# receivera.net
KiCad netlist of a schematic drawn in EAGLE
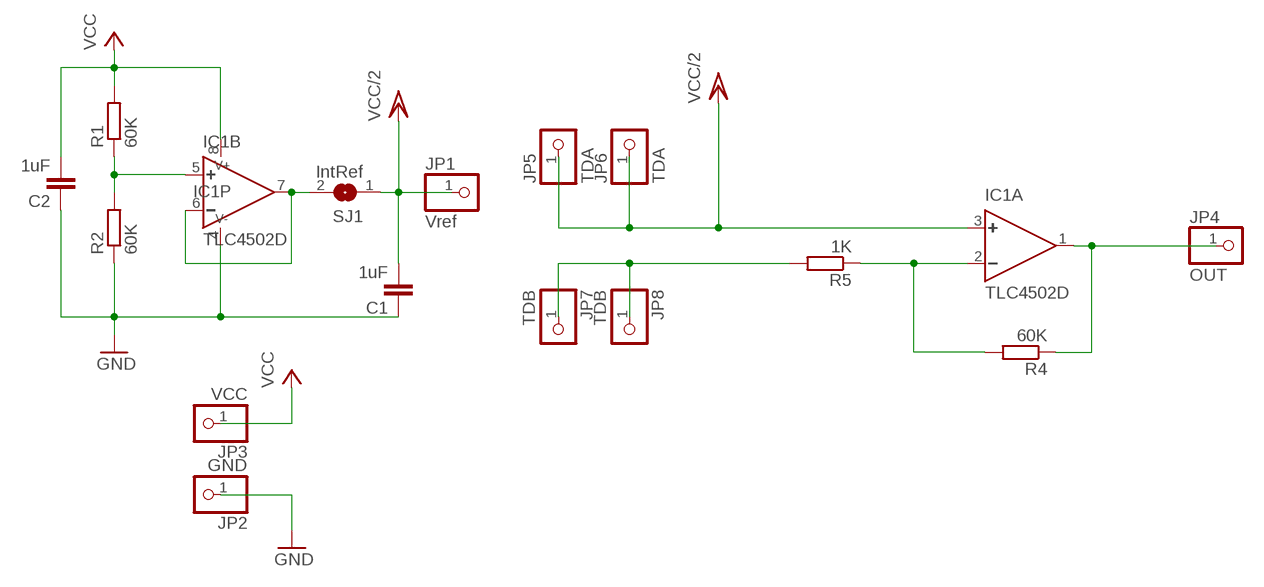
[diagram p0: schematic, sheet 1]

(export (version "E")
  (design (tool "Eeschema 10.0.6"))
  (components
    (comp (ref "C1")
      (value "1uF")
      (footprint "eagle-import:C1206")
      (libsource (lib "eagle-import") (part "C-EUC1206"))
    )
    (comp (ref "C2")
      (value "1uF")
      (footprint "eagle-import:C1206")
      (libsource (lib "eagle-import") (part "C-EUC1206"))
    )
    (comp (ref "IC1")
      (value "TLC4502D")
      (footprint "eagle-import:D_R-PDSO-G08")
      (libsource (lib "eagle-import") (part "TLC4502D"))
    )
    (comp (ref "JP1")
      (value "Vref")
      (footprint "eagle-import:1X01")
      (libsource (lib "eagle-import") (part "PINHD-1X1"))
    )
    (comp (ref "JP2")
      (value "GND")
      (footprint "eagle-import:1X01")
      (libsource (lib "eagle-import") (part "PINHD-1X1"))
    )
    (comp (ref "JP3")
      (value "VCC")
      (footprint "eagle-import:1X01")
      (libsource (lib "eagle-import") (part "PINHD-1X1"))
    )
    (comp (ref "JP4")
      (value "OUT")
      (footprint "eagle-import:1X01")
      (libsource (lib "eagle-import") (part "PINHD-1X1"))
    )
    (comp (ref "JP5")
      (value "TDA")
      (footprint "eagle-import:1X01")
      (libsource (lib "eagle-import") (part "PINHD-1X1"))
    )
    (comp (ref "JP6")
      (value "TDA")
      (footprint "eagle-import:1X01")
      (libsource (lib "eagle-import") (part "PINHD-1X1"))
    )
    (comp (ref "JP7")
      (value "TDB")
      (footprint "eagle-import:1X01")
      (libsource (lib "eagle-import") (part "PINHD-1X1"))
    )
    (comp (ref "JP8")
      (value "TDB")
      (footprint "eagle-import:1X01")
      (libsource (lib "eagle-import") (part "PINHD-1X1"))
    )
    (comp (ref "R1")
      (value "60K")
      (footprint "eagle-import:R1206")
      (libsource (lib "eagle-import") (part "R-EU_R1206"))
    )
    (comp (ref "R2")
      (value "60K")
      (footprint "eagle-import:R1206")
      (libsource (lib "eagle-import") (part "R-EU_R1206"))
    )
    (comp (ref "R4")
      (value "60K")
      (footprint "eagle-import:R1206")
      (libsource (lib "eagle-import") (part "R-EU_R1206"))
    )
    (comp (ref "R5")
      (value "1K")
      (footprint "eagle-import:R1206")
      (libsource (lib "eagle-import") (part "R-EU_R1206"))
    )
    (comp (ref "SJ1")
      (value "IntRef")
      (footprint "eagle-import:SJ")
      (libsource (lib "eagle-import") (part "SJ"))
    )
  )
  (nets
    (net (code "1") (name "GND") (class "Default")
      (node (ref "C1") (pin "1") (pinfunction "1_1") (pintype "passive"))
      (node (ref "C2") (pin "1") (pinfunction "1_1") (pintype "passive"))
      (node (ref "IC1") (pin "4") (pinfunction "V-_4") (pintype "power_in"))
      (node (ref "JP2") (pin "1") (pinfunction "1_1") (pintype "passive"))
      (node (ref "R2") (pin "1") (pinfunction "1_1") (pintype "passive"))
    )
    (net (code "2") (name "Net-(IC1A--)") (class "Default")
      (node (ref "IC1") (pin "2") (pinfunction "-_2") (pintype "input"))
      (node (ref "R4") (pin "2") (pinfunction "2_2") (pintype "passive"))
      (node (ref "R5") (pin "1") (pinfunction "1_1") (pintype "passive"))
    )
    (net (code "3") (name "Net-(IC1A-OUT)") (class "Default")
      (node (ref "IC1") (pin "1") (pinfunction "OUT_1") (pintype "output"))
      (node (ref "JP4") (pin "1") (pinfunction "1_1") (pintype "passive"))
      (node (ref "R4") (pin "1") (pinfunction "1_1") (pintype "passive"))
    )
    (net (code "4") (name "Net-(IC1B-+)") (class "Default")
      (node (ref "IC1") (pin "5") (pinfunction "+_5") (pintype "input"))
      (node (ref "R1") (pin "1") (pinfunction "1_1") (pintype "passive"))
      (node (ref "R2") (pin "2") (pinfunction "2_2") (pintype "passive"))
    )
    (net (code "5") (name "Net-(IC1B--)") (class "Default")
      (node (ref "IC1") (pin "6") (pinfunction "-_6") (pintype "input"))
      (node (ref "IC1") (pin "7") (pinfunction "OUT_7") (pintype "output"))
      (node (ref "SJ1") (pin "2") (pinfunction "2_2") (pintype "passive"))
    )
    (net (code "6") (name "Net-(JP7-Pad1)") (class "Default")
      (node (ref "JP7") (pin "1") (pinfunction "1_1") (pintype "passive"))
      (node (ref "JP8") (pin "1") (pinfunction "1_1") (pintype "passive"))
      (node (ref "R5") (pin "2") (pinfunction "2_2") (pintype "passive"))
    )
    (net (code "7") (name "VCC") (class "Default")
      (node (ref "C2") (pin "2") (pinfunction "2_2") (pintype "passive"))
      (node (ref "IC1") (pin "8") (pinfunction "V+_8") (pintype "power_in"))
      (node (ref "JP3") (pin "1") (pinfunction "1_1") (pintype "passive"))
      (node (ref "R1") (pin "2") (pinfunction "2_2") (pintype "passive"))
    )
    (net (code "8") (name "VCC{slash}2") (class "Default")
      (node (ref "C1") (pin "2") (pinfunction "2_2") (pintype "passive"))
      (node (ref "IC1") (pin "3") (pinfunction "+_3") (pintype "input"))
      (node (ref "JP1") (pin "1") (pinfunction "1_1") (pintype "passive"))
      (node (ref "JP5") (pin "1") (pinfunction "1_1") (pintype "passive"))
      (node (ref "JP6") (pin "1") (pinfunction "1_1") (pintype "passive"))
      (node (ref "SJ1") (pin "1") (pinfunction "1_1") (pintype "passive"))
    )
  )
)
